# LED_News_ticker_2021-06-20.net
KiCad netlist of a schematic drawn in EasyEDA
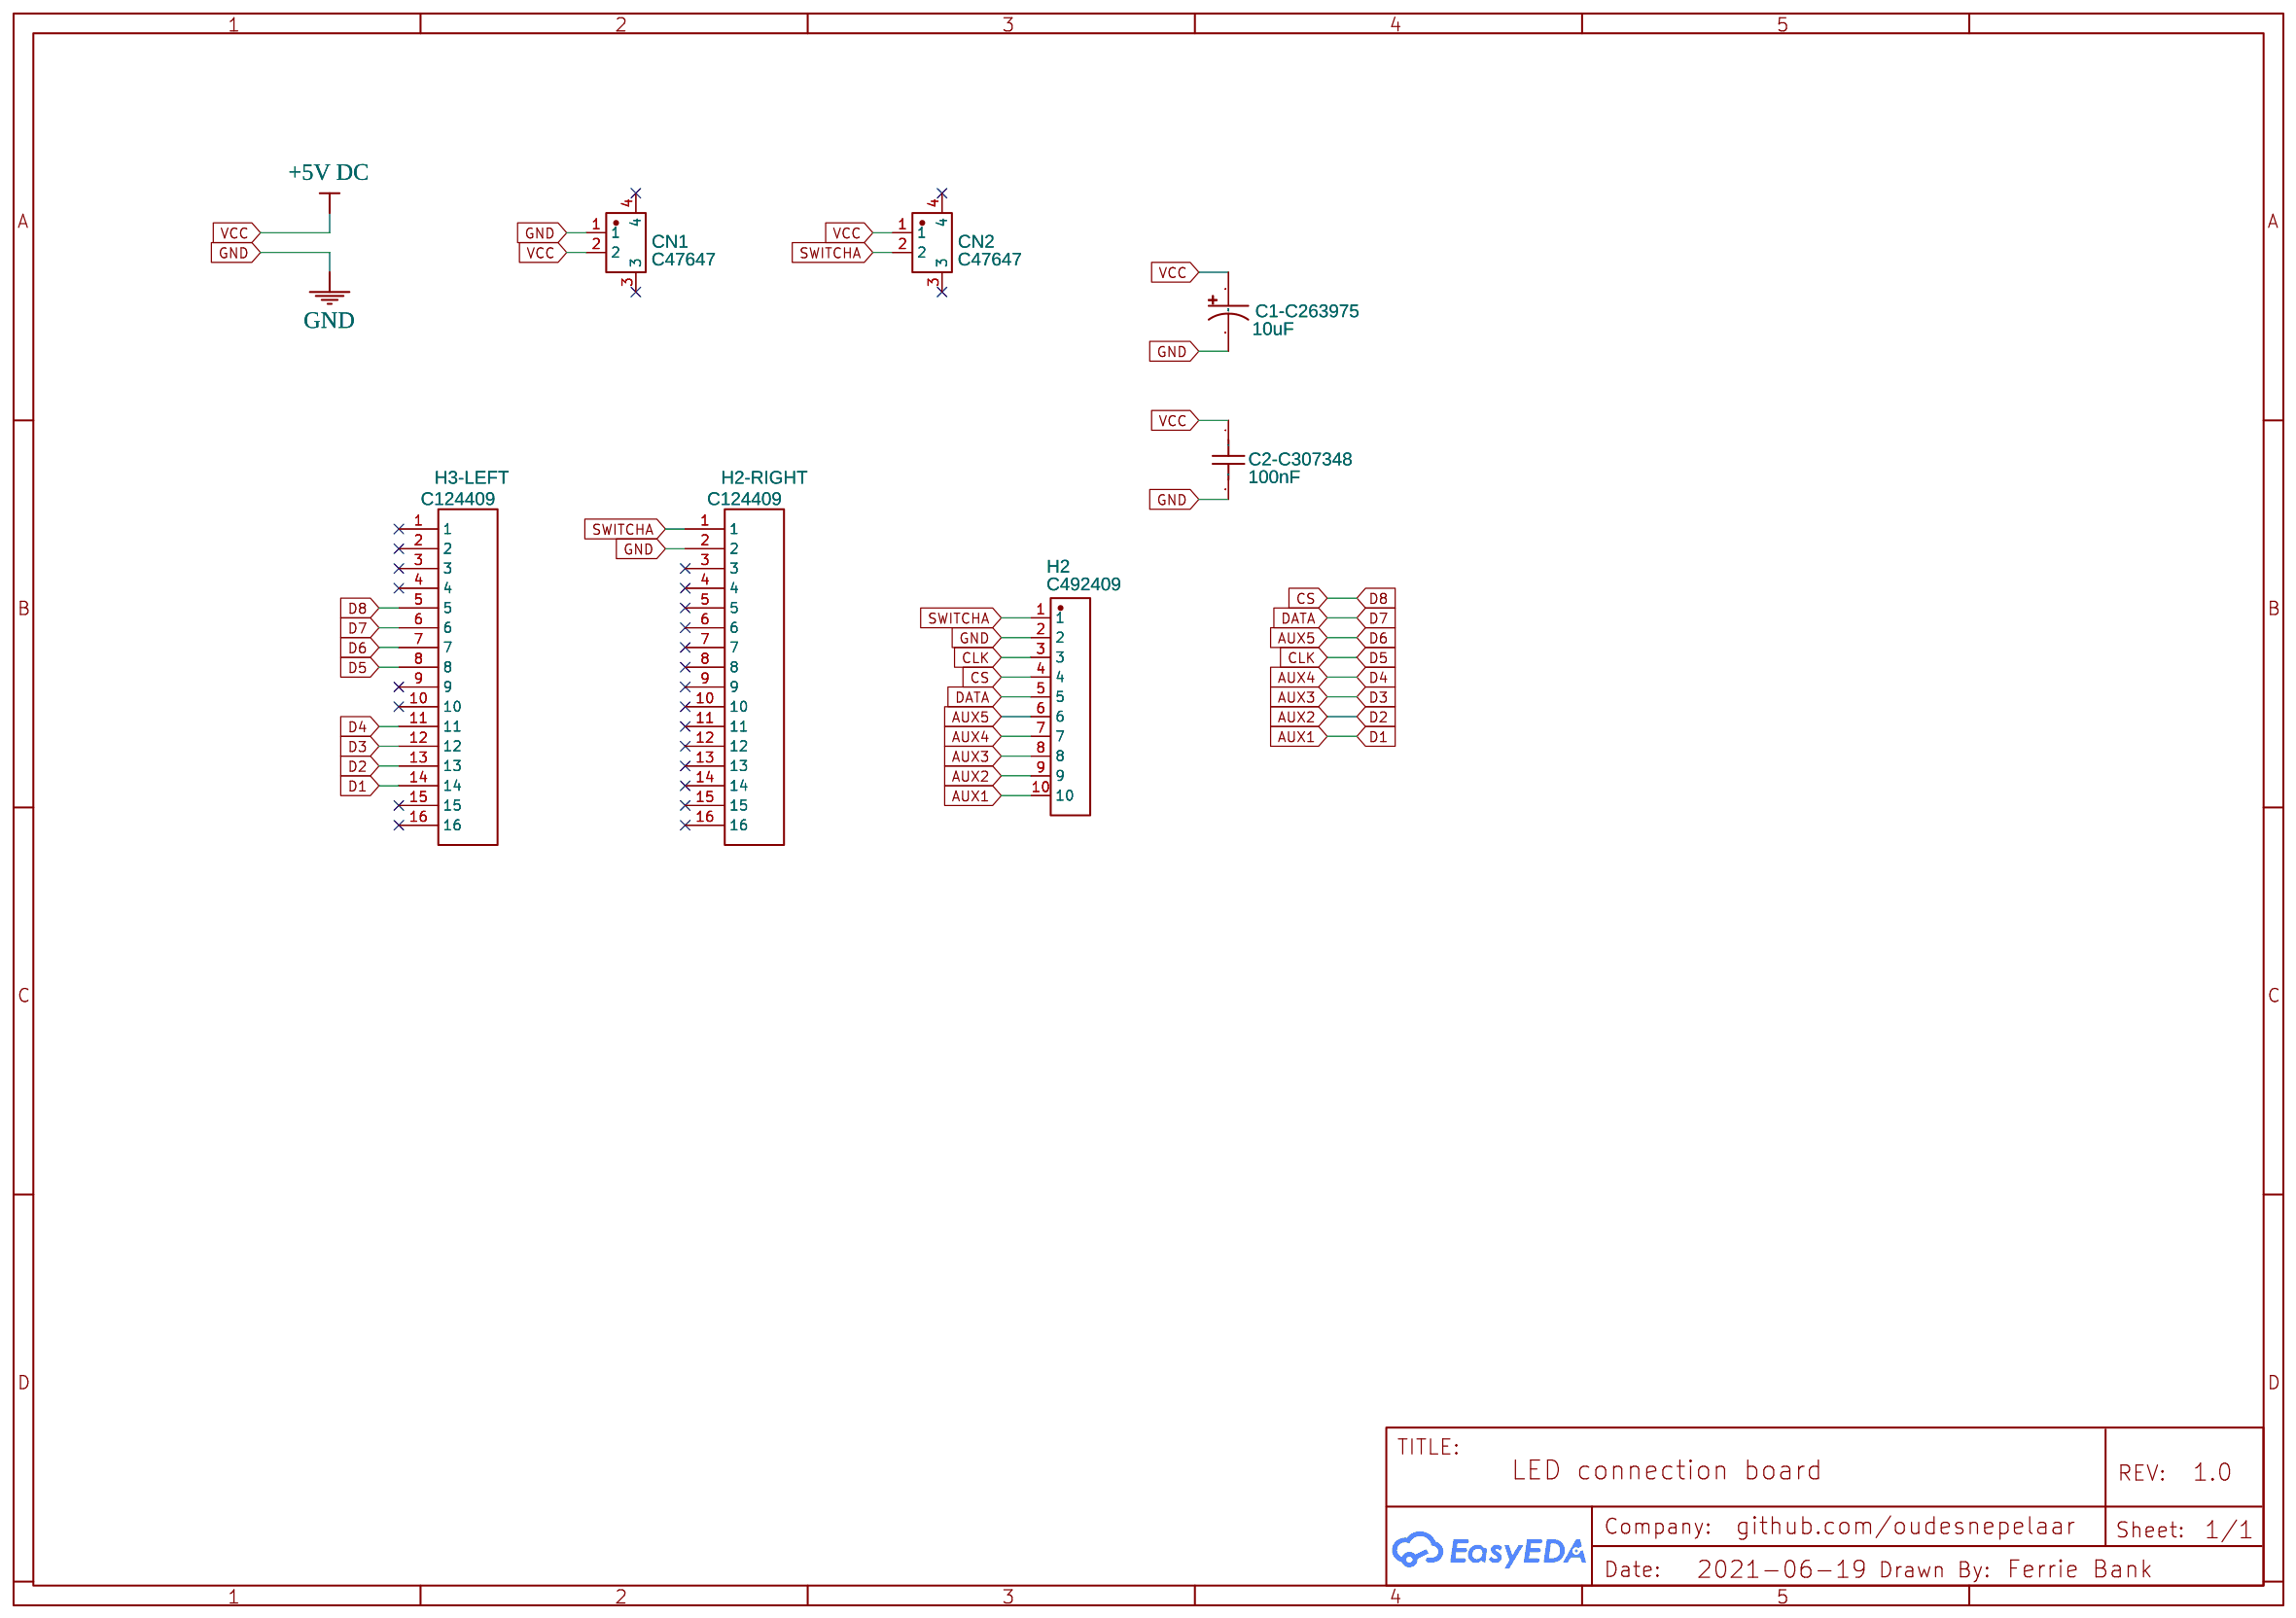
[diagram p0: schematic sheet]

(export (version "E")
  (design (tool "Eeschema 10.0.6"))
  (components
    (comp (ref "C1-C263975")
      (value "10uF")
      (fields
        (field (name "BOM_Manufacturer Part") "CK1H100MCRD54")
        (field (name "BOM_Supplier Part") "C263975")
      )
      (libsource (lib "") (part "CK1H100MCRD54"))
    )
    (comp (ref "C2-C307348")
      (value "100nF")
      (fields
        (field (name "BOM_Manufacturer Part") "CL10B104KB8WPNC")
        (field (name "BOM_Supplier Part") "C307348")
      )
      (libsource (lib "") (part "CL10B104KB8WPNC"))
    )
    (comp (ref "CN1")
      (value "C47647")
      (fields (field (name "BOM_Manufacturer Part") "PH2.0-2PWB Horizontal"))
      (libsource (lib "") (part "PH2.0-2PWB"))
    )
    (comp (ref "CN2")
      (value "C47647")
      (fields (field (name "BOM_Manufacturer Part") "PH2.0-2PWB Horizontal"))
      (libsource (lib "") (part "PH2.0-2PWB"))
    )
    (comp (ref "H2")
      (value "C492409")
      (fields (field (name "BOM_Manufacturer Part") "PZ254V-11-10P"))
      (libsource (lib "") (part "PZ254V-11-10P"))
    )
    (comp (ref "H2-RIGHT")
      (value "C124409")
      (fields (field (name "BOM_Manufacturer Part") "220S-1*16P H=8.5MM Ytype Gold-plated"))
      (libsource (lib "") (part "220S-1*16P H=8.5MM Ytype Gold-plated"))
    )
    (comp (ref "H3-LEFT")
      (value "C124409")
      (fields (field (name "BOM_Manufacturer Part") "220S-1*16P H=8.5MM Ytype Gold-plated"))
      (libsource (lib "") (part "220S-1*16P H=8.5MM Ytype Gold-plated_1"))
    )
  )
  (nets
    (net (code "1") (name "AUX1") (class "Default")
      (node (ref "H2") (pin "10") (pinfunction "10_10") (pintype "unspecified"))
      (node (ref "H3-LEFT") (pin "14") (pinfunction "14_14") (pintype "unspecified"))
    )
    (net (code "2") (name "AUX2") (class "Default")
      (node (ref "H2") (pin "9") (pinfunction "9_9") (pintype "unspecified"))
      (node (ref "H3-LEFT") (pin "13") (pinfunction "13_13") (pintype "unspecified"))
    )
    (net (code "3") (name "AUX3") (class "Default")
      (node (ref "H2") (pin "8") (pinfunction "8_8") (pintype "unspecified"))
      (node (ref "H3-LEFT") (pin "12") (pinfunction "12_12") (pintype "unspecified"))
    )
    (net (code "4") (name "AUX4") (class "Default")
      (node (ref "H2") (pin "7") (pinfunction "7_7") (pintype "unspecified"))
      (node (ref "H3-LEFT") (pin "11") (pinfunction "11_11") (pintype "unspecified"))
    )
    (net (code "5") (name "AUX5") (class "Default")
      (node (ref "H2") (pin "6") (pinfunction "6_6") (pintype "unspecified"))
      (node (ref "H3-LEFT") (pin "7") (pinfunction "7_7") (pintype "unspecified"))
    )
    (net (code "6") (name "CLK") (class "Default")
      (node (ref "H2") (pin "3") (pinfunction "3_3") (pintype "unspecified"))
      (node (ref "H3-LEFT") (pin "8") (pinfunction "8_8") (pintype "unspecified"))
    )
    (net (code "7") (name "CS") (class "Default")
      (node (ref "H2") (pin "4") (pinfunction "4_4") (pintype "unspecified"))
      (node (ref "H3-LEFT") (pin "5") (pinfunction "5_5") (pintype "unspecified"))
    )
    (net (code "8") (name "D7") (class "Default")
      (node (ref "H2") (pin "5") (pinfunction "5_5") (pintype "unspecified"))
      (node (ref "H3-LEFT") (pin "6") (pinfunction "6_6") (pintype "unspecified"))
    )
    (net (code "9") (name "GND") (class "Default")
      (node (ref "C1-C263975") (pin "2") (pinfunction "2_2") (pintype "unspecified"))
      (node (ref "C2-C307348") (pin "2") (pinfunction "2_2") (pintype "unspecified"))
      (node (ref "CN1") (pin "1") (pinfunction "1_1") (pintype "unspecified"))
      (node (ref "H2") (pin "2") (pinfunction "2_2") (pintype "unspecified"))
      (node (ref "H2-RIGHT") (pin "2") (pinfunction "2_2") (pintype "unspecified"))
    )
    (net (code "10") (name "SWITCHA") (class "Default")
      (node (ref "CN2") (pin "2") (pinfunction "2_2") (pintype "unspecified"))
      (node (ref "H2") (pin "1") (pinfunction "1_1") (pintype "unspecified"))
      (node (ref "H2-RIGHT") (pin "1") (pinfunction "1_1") (pintype "unspecified"))
    )
    (net (code "11") (name "VCC") (class "Default")
      (node (ref "C1-C263975") (pin "1") (pinfunction "1_1") (pintype "unspecified"))
      (node (ref "C2-C307348") (pin "1") (pinfunction "1_1") (pintype "unspecified"))
      (node (ref "CN1") (pin "2") (pinfunction "2_2") (pintype "unspecified"))
      (node (ref "CN2") (pin "1") (pinfunction "1_1") (pintype "unspecified"))
    )
    (net (code "12") (name "unconnected-(CN1-Pad3)") (class "Default")
      (node (ref "CN1") (pin "3") (pinfunction "3_3") (pintype "unspecified+no_connect"))
    )
    (net (code "13") (name "unconnected-(CN1-Pad4)") (class "Default")
      (node (ref "CN1") (pin "4") (pinfunction "4_4") (pintype "unspecified+no_connect"))
    )
    (net (code "14") (name "unconnected-(CN2-Pad3)") (class "Default")
      (node (ref "CN2") (pin "3") (pinfunction "3_3") (pintype "unspecified+no_connect"))
    )
    (net (code "15") (name "unconnected-(CN2-Pad4)") (class "Default")
      (node (ref "CN2") (pin "4") (pinfunction "4_4") (pintype "unspecified+no_connect"))
    )
    (net (code "16") (name "unconnected-(H2-RIGHT-Pad3)") (class "Default")
      (node (ref "H2-RIGHT") (pin "3") (pinfunction "3_3") (pintype "unspecified+no_connect"))
    )
    (net (code "17") (name "unconnected-(H2-RIGHT-Pad4)") (class "Default")
      (node (ref "H2-RIGHT") (pin "4") (pinfunction "4_4") (pintype "unspecified+no_connect"))
    )
    (net (code "18") (name "unconnected-(H2-RIGHT-Pad5)") (class "Default")
      (node (ref "H2-RIGHT") (pin "5") (pinfunction "5_5") (pintype "unspecified+no_connect"))
    )
    (net (code "19") (name "unconnected-(H2-RIGHT-Pad6)") (class "Default")
      (node (ref "H2-RIGHT") (pin "6") (pinfunction "6_6") (pintype "unspecified+no_connect"))
    )
    (net (code "20") (name "unconnected-(H2-RIGHT-Pad7)") (class "Default")
      (node (ref "H2-RIGHT") (pin "7") (pinfunction "7_7") (pintype "unspecified+no_connect"))
    )
    (net (code "21") (name "unconnected-(H2-RIGHT-Pad8)") (class "Default")
      (node (ref "H2-RIGHT") (pin "8") (pinfunction "8_8") (pintype "unspecified+no_connect"))
    )
    (net (code "22") (name "unconnected-(H2-RIGHT-Pad9)") (class "Default")
      (node (ref "H2-RIGHT") (pin "9") (pinfunction "9_9") (pintype "unspecified+no_connect"))
    )
    (net (code "23") (name "unconnected-(H2-RIGHT-Pad10)") (class "Default")
      (node (ref "H2-RIGHT") (pin "10") (pinfunction "10_10") (pintype "unspecified+no_connect"))
    )
    (net (code "24") (name "unconnected-(H2-RIGHT-Pad11)") (class "Default")
      (node (ref "H2-RIGHT") (pin "11") (pinfunction "11_11") (pintype "unspecified+no_connect"))
    )
    (net (code "25") (name "unconnected-(H2-RIGHT-Pad12)") (class "Default")
      (node (ref "H2-RIGHT") (pin "12") (pinfunction "12_12") (pintype "unspecified+no_connect"))
    )
    (net (code "26") (name "unconnected-(H2-RIGHT-Pad13)") (class "Default")
      (node (ref "H2-RIGHT") (pin "13") (pinfunction "13_13") (pintype "unspecified+no_connect"))
    )
    (net (code "27") (name "unconnected-(H2-RIGHT-Pad14)") (class "Default")
      (node (ref "H2-RIGHT") (pin "14") (pinfunction "14_14") (pintype "unspecified+no_connect"))
    )
    (net (code "28") (name "unconnected-(H2-RIGHT-Pad15)") (class "Default")
      (node (ref "H2-RIGHT") (pin "15") (pinfunction "15_15") (pintype "unspecified+no_connect"))
    )
    (net (code "29") (name "unconnected-(H2-RIGHT-Pad16)") (class "Default")
      (node (ref "H2-RIGHT") (pin "16") (pinfunction "16_16") (pintype "unspecified+no_connect"))
    )
    (net (code "30") (name "unconnected-(H3-LEFT-Pad1)") (class "Default")
      (node (ref "H3-LEFT") (pin "1") (pinfunction "1_1") (pintype "unspecified+no_connect"))
    )
    (net (code "31") (name "unconnected-(H3-LEFT-Pad2)") (class "Default")
      (node (ref "H3-LEFT") (pin "2") (pinfunction "2_2") (pintype "unspecified+no_connect"))
    )
    (net (code "32") (name "unconnected-(H3-LEFT-Pad3)") (class "Default")
      (node (ref "H3-LEFT") (pin "3") (pinfunction "3_3") (pintype "unspecified+no_connect"))
    )
    (net (code "33") (name "unconnected-(H3-LEFT-Pad4)") (class "Default")
      (node (ref "H3-LEFT") (pin "4") (pinfunction "4_4") (pintype "unspecified+no_connect"))
    )
    (net (code "34") (name "unconnected-(H3-LEFT-Pad9)") (class "Default")
      (node (ref "H3-LEFT") (pin "9") (pinfunction "9_9") (pintype "unspecified+no_connect"))
    )
    (net (code "35") (name "unconnected-(H3-LEFT-Pad10)") (class "Default")
      (node (ref "H3-LEFT") (pin "10") (pinfunction "10_10") (pintype "unspecified+no_connect"))
    )
    (net (code "36") (name "unconnected-(H3-LEFT-Pad15)") (class "Default")
      (node (ref "H3-LEFT") (pin "15") (pinfunction "15_15") (pintype "unspecified+no_connect"))
    )
    (net (code "37") (name "unconnected-(H3-LEFT-Pad16)") (class "Default")
      (node (ref "H3-LEFT") (pin "16") (pinfunction "16_16") (pintype "unspecified+no_connect"))
    )
  )
)
